# High_Power.net
KiCad netlist of a schematic drawn in Altium Designer
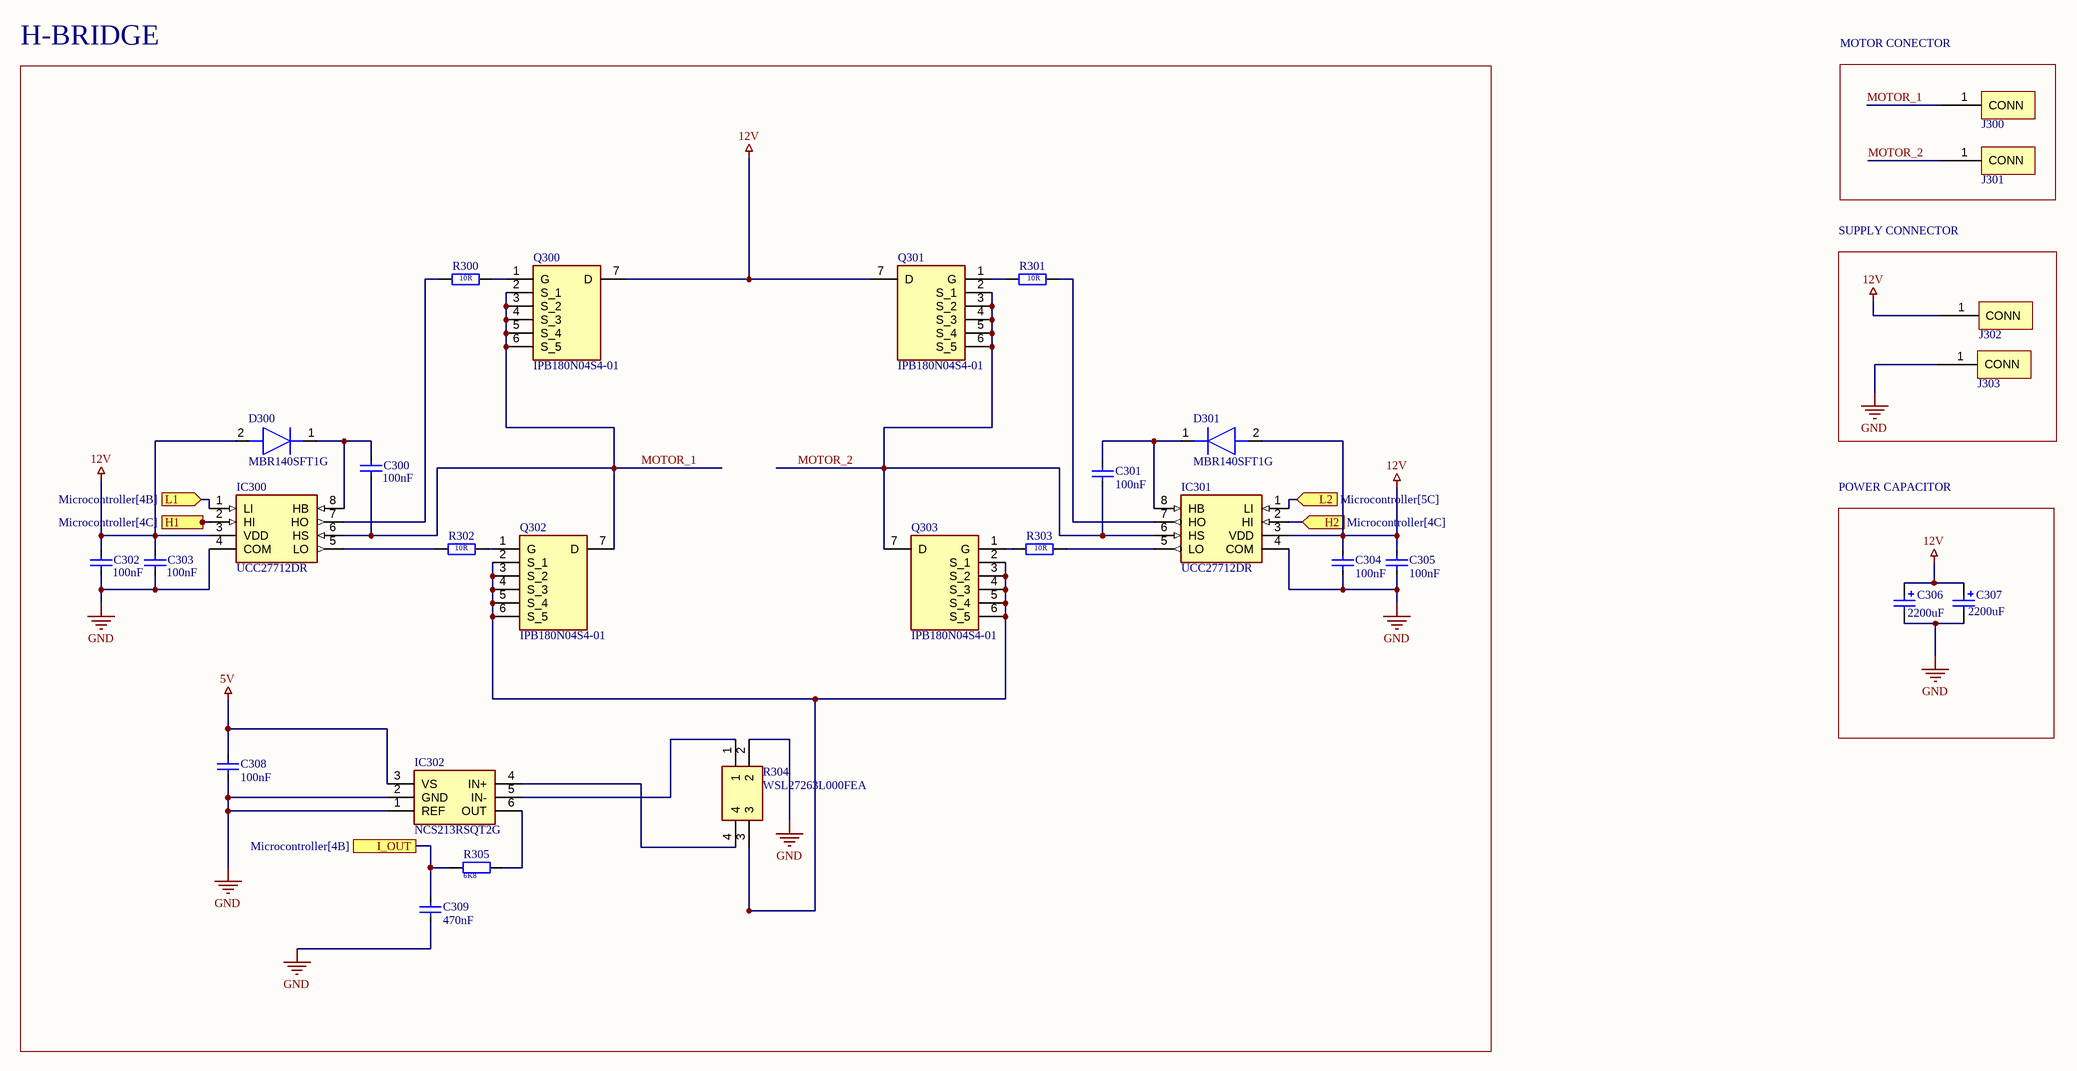
[diagram p0: High_Power.SchDoc]

(export (version "E")
  (design (tool "Eeschema 10.0.6"))
  (components
    (comp (ref "C300")
      (value "100nF")
      (footprint "CAPC1608X09N")
      (fields (field (name "MPN") "06033C104KAT4A") (field (name "Comment") "C"))
      (libsource (lib "My_lib") (part "C"))
    )
    (comp (ref "C301")
      (value "100nF")
      (footprint "CAPC1608X09N")
      (fields (field (name "MPN") "06033C104KAT4A") (field (name "Comment") "C"))
      (libsource (lib "My_lib") (part "C"))
    )
    (comp (ref "C302")
      (value "100nF")
      (footprint "CAPC1608X09N")
      (fields (field (name "MPN") "06033C104KAT4A") (field (name "Comment") "C"))
      (libsource (lib "My_lib") (part "C"))
    )
    (comp (ref "C303")
      (value "100nF")
      (footprint "CAPC1608X09N")
      (fields (field (name "MPN") "06033C104KAT4A") (field (name "Comment") "C"))
      (libsource (lib "My_lib") (part "C"))
    )
    (comp (ref "C304")
      (value "100nF")
      (footprint "CAPC1608X09N")
      (fields (field (name "MPN") "06033C104KAT4A") (field (name "Comment") "C"))
      (libsource (lib "My_lib") (part "C"))
    )
    (comp (ref "C305")
      (value "100nF")
      (footprint "CAPC1608X09N")
      (fields (field (name "MPN") "06033C104KAT4A") (field (name "Comment") "C"))
      (libsource (lib "My_lib") (part "C"))
    )
    (comp (ref "C306")
      (value "2200uF")
      (footprint "Capacitor_12.5_20_5mm")
      (fields (field (name "MPN") "LKML2001E222MF") (field (name "Comment") "Capacitor_12.5_20_5mm"))
      (libsource (lib "My_lib") (part "Capacitor_12.5_20_5mm"))
    )
    (comp (ref "C307")
      (value "2200uF")
      (footprint "Capacitor_12.5_20_5mm")
      (fields (field (name "MPN") "LKML2001E222MF") (field (name "Comment") "Capacitor_12.5_20_5mm"))
      (libsource (lib "My_lib") (part "Capacitor_12.5_20_5mm"))
    )
    (comp (ref "C308")
      (value "100nF")
      (footprint "CAPC1608X09N")
      (fields (field (name "MPN") "06033C104KAT4A") (field (name "Comment") "C"))
      (libsource (lib "My_lib") (part "C"))
    )
    (comp (ref "C309")
      (value "470nF")
      (footprint "CAPC1608X09N")
      (fields (field (name "MPN") "CS1608X7R474K250NRB") (field (name "Comment") "C"))
      (libsource (lib "My_lib") (part "C"))
    )
    (comp (ref "D300")
      (value "MBR140SFT1G")
      (footprint "SamacSys:SODFL3616X98N")
      (description "Diode")
      (fields (field (name "LCSC PART NUMBER") "C43381"))
      (libsource (lib "SamacSys") (part "MBR140SFT1G"))
    )
    (comp (ref "D301")
      (value "MBR140SFT1G")
      (footprint "SamacSys:SODFL3616X98N")
      (description "Diode")
      (fields (field (name "LCSC PART NUMBER") "C43381"))
      (libsource (lib "SamacSys") (part "MBR140SFT1G"))
    )
    (comp (ref "IC300")
      (value "UCC27712DR")
      (footprint "SamacSys:SOIC127P600X175-8N")
      (description "Integrated Circuit")
      (fields (field (name "LCSC PART NUMBER") "C485818"))
      (libsource (lib "") (part "UCC27712DR_1"))
    )
    (comp (ref "IC301")
      (value "UCC27712DR")
      (footprint "SamacSys:SOIC127P600X175-8N")
      (description "Integrated Circuit")
      (fields (field (name "LCSC PART NUMBER") "C485818"))
      (libsource (lib "SamacSys") (part "UCC27712DR"))
    )
    (comp (ref "IC302")
      (value "NCS213RSQT2G")
      (footprint "SamacSys:SOT65P210X110-6N")
      (description "Integrated Circuit")
      (fields (field (name "LCSC PART NUMBER") "863-NCS213RSQT2G"))
      (libsource (lib "SamacSys") (part "NCS213RSQT2G"))
    )
    (comp (ref "J300")
      (value "PCB_CONN")
      (footprint "T54105100-1050")
      (fields (field (name "MPN") "T54105100-1050") (field (name "MANUFACTURER") "XFCN"))
      (libsource (lib "My_lib") (part "PCB_CONN"))
    )
    (comp (ref "J301")
      (value "PCB_CONN")
      (footprint "T54105100-1050")
      (fields (field (name "MPN") "T54105100-1050") (field (name "MANUFACTURER") "XFCN"))
      (libsource (lib "My_lib") (part "PCB_CONN"))
    )
    (comp (ref "J302")
      (value "PCB_CONN")
      (footprint "T54105100-1050")
      (fields (field (name "MPN") "T54105100-1050") (field (name "MANUFACTURER") "XFCN"))
      (libsource (lib "My_lib") (part "PCB_CONN"))
    )
    (comp (ref "J303")
      (value "PCB_CONN")
      (footprint "T54105100-1050")
      (fields (field (name "MPN") "T54105100-1050") (field (name "MANUFACTURER") "XFCN"))
      (libsource (lib "My_lib") (part "PCB_CONN"))
    )
    (comp (ref "Q300")
      (value "IPB180N04S4-01")
      (footprint "SamacSys:IPB240N04S4R9ATMA1")
      (description "MOSFET (N-Channel)")
      (fields (field (name "LCSC PART NUMBER") "C536569"))
      (libsource (lib "") (part "IRFS3107-7PPBF_1"))
    )
    (comp (ref "Q301")
      (value "IPB180N04S4-01")
      (footprint "SamacSys:IPB240N04S4R9ATMA1")
      (description "MOSFET (N-Channel)")
      (fields (field (name "LCSC PART NUMBER") "C536569"))
      (libsource (lib "*") (part "IRFS3107-7PPBF"))
    )
    (comp (ref "Q302")
      (value "IPB180N04S4-01")
      (footprint "SamacSys:IPB240N04S4R9ATMA1")
      (description "MOSFET (N-Channel)")
      (fields (field (name "LCSC PART NUMBER") "C536569"))
      (libsource (lib "") (part "IRFS3107-7PPBF_1"))
    )
    (comp (ref "Q303")
      (value "IPB180N04S4-01")
      (footprint "SamacSys:IPB240N04S4R9ATMA1")
      (description "MOSFET (N-Channel)")
      (fields (field (name "LCSC PART NUMBER") "C536569"))
      (libsource (lib "*") (part "IRFS3107-7PPBF"))
    )
    (comp (ref "R300")
      (value "10R")
      (footprint "RESC3216X07N")
      (fields (field (name "MPN") "1206W4F100JT5E") (field (name "Comment") "R"))
      (libsource (lib "My_lib") (part "R"))
    )
    (comp (ref "R301")
      (value "10R")
      (footprint "RESC3216X07N")
      (fields (field (name "MPN") "1206W4F100JT5E") (field (name "Comment") "R"))
      (libsource (lib "") (part "R_1"))
    )
    (comp (ref "R302")
      (value "10R")
      (footprint "RESC3216X07N")
      (fields (field (name "MPN") "1206W4F100JT5E") (field (name "Comment") "R"))
      (libsource (lib "My_lib") (part "R"))
    )
    (comp (ref "R303")
      (value "10R")
      (footprint "RESC3216X07N")
      (fields (field (name "MPN") "1206W4F100JT5E") (field (name "Comment") "R"))
      (libsource (lib "") (part "R_1"))
    )
    (comp (ref "R304")
      (value "WSL27263L000FEA")
      (footprint "SamacSys:WSL27263L000FEA")
      (description "Resistor")
      (fields (field (name "MPN") "SBB-K-3J-n-t1") (field (name "LCSC PART NUMBER") "C503796"))
      (libsource (lib "SamacSys") (part "WSL27263L000FEA"))
    )
    (comp (ref "R305")
      (value "6K8")
      (footprint "RESC1608X06N")
      (fields (field (name "MPN") "RC0603FR-076K8L") (field (name "Comment") "R"))
      (libsource (lib "") (part "R_1"))
    )
  )
  (nets
    (net (code "1") (name "/H1") (class "Default")
      (node (ref "IC300") (pin "2") (pinfunction "HI_2") (pintype "input"))
    )
    (net (code "2") (name "/H2") (class "Default")
      (node (ref "IC301") (pin "2") (pinfunction "HI_2") (pintype "input"))
    )
    (net (code "3") (name "/I_OUT") (class "Default")
      (node (ref "C309") (pin "1") (pinfunction "1_1") (pintype "passive"))
      (node (ref "R305") (pin "2") (pinfunction "2_2") (pintype "passive"))
    )
    (net (code "4") (name "/L1") (class "Default")
      (node (ref "IC300") (pin "1") (pinfunction "LI_1") (pintype "input"))
    )
    (net (code "5") (name "/L2") (class "Default")
      (node (ref "IC301") (pin "1") (pinfunction "LI_1") (pintype "input"))
    )
    (net (code "6") (name "/MOTOR_1") (class "Default")
      (node (ref "C300") (pin "1") (pinfunction "1_1") (pintype "passive"))
      (node (ref "IC300") (pin "6") (pinfunction "HS_6") (pintype "input"))
      (node (ref "J300") (pin "1") (pinfunction "CONN_1") (pintype "passive"))
      (node (ref "Q300") (pin "2") (pinfunction "S_1_2") (pintype "passive"))
      (node (ref "Q300") (pin "3") (pinfunction "S_2_3") (pintype "passive"))
      (node (ref "Q300") (pin "4") (pinfunction "S_3_4") (pintype "passive"))
      (node (ref "Q300") (pin "5") (pinfunction "S_4_5") (pintype "passive"))
      (node (ref "Q300") (pin "6") (pinfunction "S_5_6") (pintype "passive"))
      (node (ref "Q302") (pin "7") (pinfunction "D_7") (pintype "passive"))
    )
    (net (code "7") (name "/MOTOR_2") (class "Default")
      (node (ref "C301") (pin "1") (pinfunction "1_1") (pintype "passive"))
      (node (ref "IC301") (pin "6") (pinfunction "HS_6") (pintype "input"))
      (node (ref "J301") (pin "1") (pinfunction "CONN_1") (pintype "passive"))
      (node (ref "Q301") (pin "2") (pinfunction "S_1_2") (pintype "passive"))
      (node (ref "Q301") (pin "3") (pinfunction "S_2_3") (pintype "passive"))
      (node (ref "Q301") (pin "4") (pinfunction "S_3_4") (pintype "passive"))
      (node (ref "Q301") (pin "5") (pinfunction "S_4_5") (pintype "passive"))
      (node (ref "Q301") (pin "6") (pinfunction "S_5_6") (pintype "passive"))
      (node (ref "Q303") (pin "7") (pinfunction "D_7") (pintype "passive"))
    )
    (net (code "8") (name "5V") (class "Default")
      (node (ref "C308") (pin "2") (pinfunction "2_2") (pintype "passive"))
      (node (ref "IC302") (pin "3") (pinfunction "VS_3") (pintype "passive"))
    )
    (net (code "9") (name "12V") (class "Default")
      (node (ref "C302") (pin "2") (pinfunction "2_2") (pintype "passive"))
      (node (ref "C303") (pin "2") (pinfunction "2_2") (pintype "passive"))
      (node (ref "C304") (pin "2") (pinfunction "2_2") (pintype "passive"))
      (node (ref "C305") (pin "2") (pinfunction "2_2") (pintype "passive"))
      (node (ref "C306") (pin "1") (pinfunction "1_1") (pintype "passive"))
      (node (ref "C307") (pin "1") (pinfunction "1_1") (pintype "passive"))
      (node (ref "D300") (pin "2") (pinfunction "A_2") (pintype "passive"))
      (node (ref "D301") (pin "2") (pinfunction "A_2") (pintype "passive"))
      (node (ref "IC300") (pin "3") (pinfunction "VDD_3") (pintype "power_in"))
      (node (ref "IC301") (pin "3") (pinfunction "VDD_3") (pintype "power_in"))
      (node (ref "J302") (pin "1") (pinfunction "CONN_1") (pintype "passive"))
      (node (ref "Q300") (pin "7") (pinfunction "D_7") (pintype "passive"))
      (node (ref "Q301") (pin "7") (pinfunction "D_7") (pintype "passive"))
    )
    (net (code "10") (name "GND") (class "Default")
      (node (ref "C302") (pin "1") (pinfunction "1_1") (pintype "passive"))
      (node (ref "C303") (pin "1") (pinfunction "1_1") (pintype "passive"))
      (node (ref "C304") (pin "1") (pinfunction "1_1") (pintype "passive"))
      (node (ref "C305") (pin "1") (pinfunction "1_1") (pintype "passive"))
      (node (ref "C306") (pin "2") (pinfunction "2_2") (pintype "passive"))
      (node (ref "C307") (pin "2") (pinfunction "2_2") (pintype "passive"))
      (node (ref "C308") (pin "1") (pinfunction "1_1") (pintype "passive"))
      (node (ref "C309") (pin "2") (pinfunction "2_2") (pintype "passive"))
      (node (ref "IC300") (pin "4") (pinfunction "COM_4") (pintype "power_in"))
      (node (ref "IC301") (pin "4") (pinfunction "COM_4") (pintype "power_in"))
      (node (ref "IC302") (pin "1") (pinfunction "REF_1") (pintype "passive"))
      (node (ref "IC302") (pin "2") (pinfunction "GND_2") (pintype "passive"))
      (node (ref "J303") (pin "1") (pinfunction "CONN_1") (pintype "passive"))
      (node (ref "R304") (pin "2") (pinfunction "2_2") (pintype "passive"))
    )
    (net (code "11") (name "Net-(D300-K)") (class "Default")
      (node (ref "C300") (pin "2") (pinfunction "2_2") (pintype "passive"))
      (node (ref "D300") (pin "1") (pinfunction "K_1") (pintype "passive"))
      (node (ref "IC300") (pin "8") (pinfunction "HB_8") (pintype "input"))
    )
    (net (code "12") (name "Net-(D301-K)") (class "Default")
      (node (ref "C301") (pin "2") (pinfunction "2_2") (pintype "passive"))
      (node (ref "D301") (pin "1") (pinfunction "K_1") (pintype "passive"))
      (node (ref "IC301") (pin "8") (pinfunction "HB_8") (pintype "input"))
    )
    (net (code "13") (name "Net-(IC300-HO)") (class "Default")
      (node (ref "IC300") (pin "7") (pinfunction "HO_7") (pintype "output"))
      (node (ref "R300") (pin "1") (pinfunction "1_1") (pintype "passive"))
    )
    (net (code "14") (name "Net-(IC300-LO)") (class "Default")
      (node (ref "IC300") (pin "5") (pinfunction "LO_5") (pintype "output"))
      (node (ref "R302") (pin "1") (pinfunction "1_1") (pintype "passive"))
    )
    (net (code "15") (name "Net-(IC301-HO)") (class "Default")
      (node (ref "IC301") (pin "7") (pinfunction "HO_7") (pintype "output"))
      (node (ref "R301") (pin "1") (pinfunction "1_1") (pintype "passive"))
    )
    (net (code "16") (name "Net-(IC301-LO)") (class "Default")
      (node (ref "IC301") (pin "5") (pinfunction "LO_5") (pintype "output"))
      (node (ref "R303") (pin "1") (pinfunction "1_1") (pintype "passive"))
    )
    (net (code "17") (name "Net-(IC302-IN+)") (class "Default")
      (node (ref "IC302") (pin "4") (pinfunction "IN+_4") (pintype "passive"))
      (node (ref "R304") (pin "4") (pinfunction "4_4") (pintype "passive"))
    )
    (net (code "18") (name "Net-(IC302-IN-)") (class "Default")
      (node (ref "IC302") (pin "5") (pinfunction "IN-_5") (pintype "passive"))
      (node (ref "R304") (pin "1") (pinfunction "1_1") (pintype "passive"))
    )
    (net (code "19") (name "Net-(IC302-OUT)") (class "Default")
      (node (ref "IC302") (pin "6") (pinfunction "OUT_6") (pintype "passive"))
      (node (ref "R305") (pin "1") (pinfunction "1_1") (pintype "passive"))
    )
    (net (code "20") (name "Net-(Q300-G)") (class "Default")
      (node (ref "Q300") (pin "1") (pinfunction "G_1") (pintype "passive"))
      (node (ref "R300") (pin "2") (pinfunction "2_2") (pintype "passive"))
    )
    (net (code "21") (name "Net-(Q301-G)") (class "Default")
      (node (ref "Q301") (pin "1") (pinfunction "G_1") (pintype "passive"))
      (node (ref "R301") (pin "2") (pinfunction "2_2") (pintype "passive"))
    )
    (net (code "22") (name "Net-(Q302-G)") (class "Default")
      (node (ref "Q302") (pin "1") (pinfunction "G_1") (pintype "passive"))
      (node (ref "R302") (pin "2") (pinfunction "2_2") (pintype "passive"))
    )
    (net (code "23") (name "Net-(Q302-S_1)") (class "Default")
      (node (ref "Q302") (pin "2") (pinfunction "S_1_2") (pintype "passive"))
      (node (ref "Q302") (pin "3") (pinfunction "S_2_3") (pintype "passive"))
      (node (ref "Q302") (pin "4") (pinfunction "S_3_4") (pintype "passive"))
      (node (ref "Q302") (pin "5") (pinfunction "S_4_5") (pintype "passive"))
      (node (ref "Q302") (pin "6") (pinfunction "S_5_6") (pintype "passive"))
      (node (ref "Q303") (pin "2") (pinfunction "S_1_2") (pintype "passive"))
      (node (ref "Q303") (pin "3") (pinfunction "S_2_3") (pintype "passive"))
      (node (ref "Q303") (pin "4") (pinfunction "S_3_4") (pintype "passive"))
      (node (ref "Q303") (pin "5") (pinfunction "S_4_5") (pintype "passive"))
      (node (ref "Q303") (pin "6") (pinfunction "S_5_6") (pintype "passive"))
      (node (ref "R304") (pin "3") (pinfunction "3_3") (pintype "passive"))
    )
    (net (code "24") (name "Net-(Q303-G)") (class "Default")
      (node (ref "Q303") (pin "1") (pinfunction "G_1") (pintype "passive"))
      (node (ref "R303") (pin "2") (pinfunction "2_2") (pintype "passive"))
    )
  )
)
